# KeeWatch_Power_Supply.net
KiCad netlist of a schematic drawn in Altium Designer
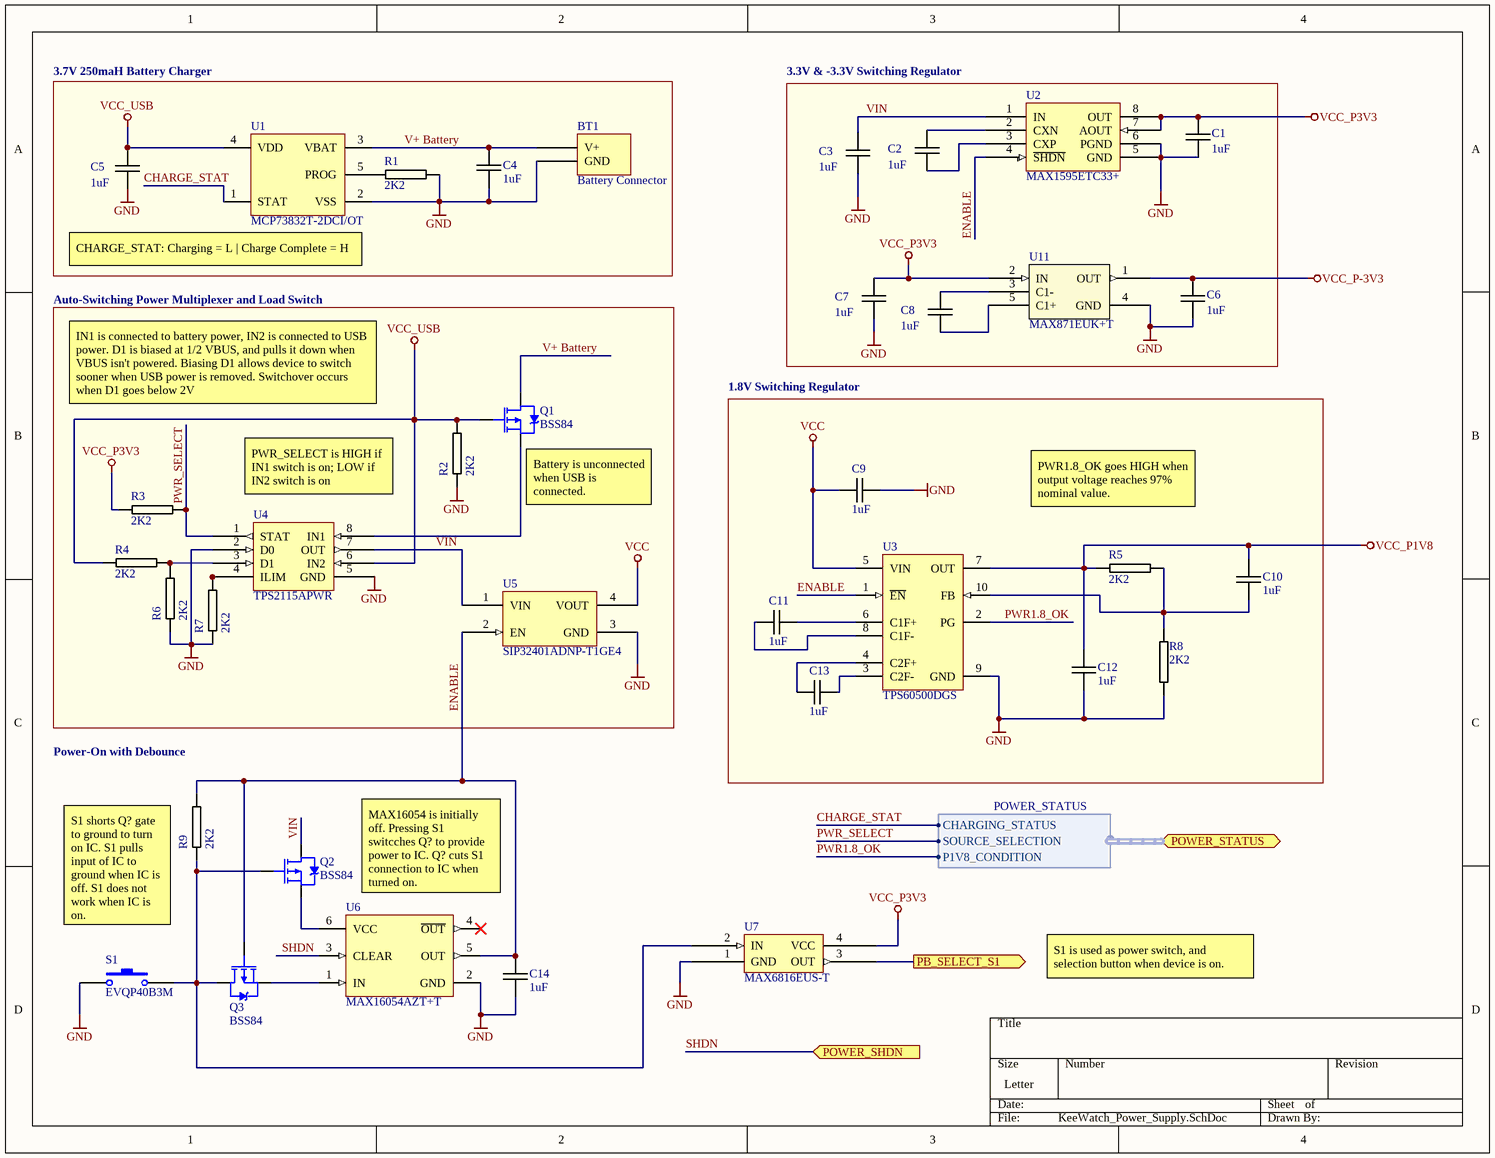
[diagram p0: KeeWatch_Power_Supply.SchDoc]

(export (version "E")
  (design (tool "Eeschema 10.0.6"))
  (components
    (comp (ref "BT1")
      (value "Battery Connector")
      (footprint "BATTERY CONNECTOR")
      (description "3.7V 250maH Battery Connector")
      (libsource (lib "WATCH") (part "Battery Connector"))
    )
    (comp (ref "C1")
      (value "1uF")
      (footprint "0603-Cap")
      (description "CAPACITOR 0603 CERAMIC")
      (libsource (lib "Passives") (part "0603-Cap"))
    )
    (comp (ref "C2")
      (value "1uF")
      (footprint "0603-Cap")
      (description "CAPACITOR 0603 CERAMIC")
      (libsource (lib "Passives") (part "0603-Cap"))
    )
    (comp (ref "C3")
      (value "1uF")
      (footprint "0603-Cap")
      (description "CAPACITOR 0603 CERAMIC")
      (libsource (lib "Passives") (part "0603-Cap"))
    )
    (comp (ref "C4")
      (value "1uF")
      (footprint "0603-Cap")
      (description "CAPACITOR 0603 CERAMIC")
      (libsource (lib "Passives") (part "0603-Cap"))
    )
    (comp (ref "C5")
      (value "1uF")
      (footprint "0603-Cap")
      (description "CAPACITOR 0603 CERAMIC")
      (libsource (lib "Passives") (part "0603-Cap"))
    )
    (comp (ref "C6")
      (value "1uF")
      (footprint "0603-Cap")
      (description "CAPACITOR 0603 CERAMIC")
      (libsource (lib "Passives") (part "0603-Cap"))
    )
    (comp (ref "C7")
      (value "1uF")
      (footprint "0603-Cap")
      (description "CAPACITOR 0603 CERAMIC")
      (libsource (lib "Passives") (part "0603-Cap"))
    )
    (comp (ref "C8")
      (value "1uF")
      (footprint "0603-Cap")
      (description "CAPACITOR 0603 CERAMIC")
      (libsource (lib "Passives") (part "0603-Cap"))
    )
    (comp (ref "C9")
      (value "1uF")
      (footprint "0603-Cap")
      (description "CAPACITOR 0603 CERAMIC")
      (libsource (lib "Passives") (part "0603-Cap"))
    )
    (comp (ref "C10")
      (value "1uF")
      (footprint "0603-Cap")
      (description "CAPACITOR 0603 CERAMIC")
      (libsource (lib "Passives") (part "0603-Cap"))
    )
    (comp (ref "C11")
      (value "1uF")
      (footprint "0603-Cap")
      (description "CAPACITOR 0603 CERAMIC")
      (libsource (lib "Passives") (part "0603-Cap"))
    )
    (comp (ref "C12")
      (value "1uF")
      (footprint "0603-Cap")
      (description "CAPACITOR 0603 CERAMIC")
      (libsource (lib "Passives") (part "0603-Cap"))
    )
    (comp (ref "C13")
      (value "1uF")
      (footprint "0603-Cap")
      (description "CAPACITOR 0603 CERAMIC")
      (libsource (lib "Passives") (part "0603-Cap"))
    )
    (comp (ref "C14")
      (value "1uF")
      (footprint "0603-Cap")
      (description "CAPACITOR 0603 CERAMIC")
      (libsource (lib "Passives") (part "0603-Cap"))
    )
    (comp (ref "Q1") (value "BSS84") (footprint "SOT23-GDS") (libsource (lib "WATCH") (part "BSS84")))
    (comp (ref "Q2") (value "BSS84") (footprint "SOT23-GDS") (libsource (lib "WATCH") (part "BSS84")))
    (comp (ref "Q3") (value "BSS84") (footprint "SOT23-GDS") (libsource (lib "WATCH") (part "BSS84")))
    (comp (ref "R1")
      (value "2K2")
      (footprint "0603-RES")
      (description "GENERIC RESISTOR 0603")
      (libsource (lib "Passives") (part "0603-Res"))
    )
    (comp (ref "R2")
      (value "2K2")
      (footprint "0603-RES")
      (description "GENERIC RESISTOR 0603")
      (libsource (lib "Passives") (part "0603-Res"))
    )
    (comp (ref "R3")
      (value "2K2")
      (footprint "0603-RES")
      (description "GENERIC RESISTOR 0603")
      (libsource (lib "Passives") (part "0603-Res"))
    )
    (comp (ref "R4")
      (value "2K2")
      (footprint "0603-RES")
      (description "GENERIC RESISTOR 0603")
      (libsource (lib "Passives") (part "0603-Res"))
    )
    (comp (ref "R5")
      (value "2K2")
      (footprint "0603-RES")
      (description "GENERIC RESISTOR 0603")
      (libsource (lib "Passives") (part "0603-Res"))
    )
    (comp (ref "R6")
      (value "2K2")
      (footprint "0603-RES")
      (description "GENERIC RESISTOR 0603")
      (libsource (lib "Passives") (part "0603-Res"))
    )
    (comp (ref "R7")
      (value "2K2")
      (footprint "0603-RES")
      (description "GENERIC RESISTOR 0603")
      (libsource (lib "Passives") (part "0603-Res"))
    )
    (comp (ref "R8")
      (value "2K2")
      (footprint "0603-RES")
      (description "GENERIC RESISTOR 0603")
      (libsource (lib "Passives") (part "0603-Res"))
    )
    (comp (ref "R9")
      (value "2K2")
      (footprint "0603-RES")
      (description "GENERIC RESISTOR 0603")
      (libsource (lib "Passives") (part "0603-Res"))
    )
    (comp (ref "S1") (value "EVQP40B3M") (footprint "EVQP4") (libsource (lib "WATCH") (part "EVQP40B3M")))
    (comp (ref "U1")
      (value "MCP73832T-2DCI/OT")
      (footprint "SOT-23-OT5_N")
      (fields (field (name "MANUFACTURER") "Microchip"))
      (libsource (lib "WATCH") (part "MCP73832T-2DCI/OT"))
    )
    (comp (ref "U2")
      (value "MAX1595ETC33+")
      (footprint "TQFN12")
      (description "Regulated 3.3V/5.0V Step-Up/Step-Down Charge Pump")
      (libsource (lib "WATCH") (part "MAX1595ETC33+"))
    )
    (comp (ref "U3")
      (value "TPS60500DGS")
      (footprint "TI-DGS10_N")
      (fields (field (name "MANUFACTURER") "Texas Instruments"))
      (libsource (lib "WATCH") (part "TPS60500DGS"))
    )
    (comp (ref "U4")
      (value "TPS2115APWR")
      (footprint "TSSOP-8")
      (description "Auto-switching Power MUX")
      (libsource (lib "WATCH") (part "TPS2115APWR"))
    )
    (comp (ref "U5")
      (value "SIP32401ADNP-T1GE4")
      (footprint "TDFN4")
      (description "1.1 V to 5.5 V, Slew Rate Controlled Load SwitcH")
      (libsource (lib "WATCH") (part "SIP32401ADNP-T1GE4"))
    )
    (comp (ref "U6")
      (value "MAX16054AZT+T")
      (footprint "Z6+1_N")
      (libsource (lib "WATCH") (part "MAX16054AZT+T"))
    )
    (comp (ref "U7")
      (value "MAX6816EUS-T")
      (footprint "SOT143B")
      (libsource (lib "Schlib2") (part "MAX6816EUS-T"))
    )
    (comp (ref "U11")
      (value "MAX871EUK+T")
      (footprint "SOT-23-OT5_N")
      (description "Switched-Capacitor Voltage Inverters")
      (fields (field (name "MANUFACTURER_PART_NUMBER") "max871euk+t"))
      (libsource (lib "WATCH") (part "MAX871EUK+T"))
    )
  )
  (nets
    (net (code "2") (name "/CHARGE_STAT") (class "Default")
      (node (ref "U1") (pin "1") (pinfunction "STAT_1") (pintype "open_collector"))
    )
    (net (code "3") (name "/ENABLE") (class "Default")
      (node (ref "C14") (pin "1") (pintype "passive"))
      (node (ref "Q3") (pin "1") (pinfunction "G_1") (pintype "passive"))
      (node (ref "R9") (pin "1") (pintype "passive"))
      (node (ref "U2") (pin "4") (pinfunction "~{SHDN}_4") (pintype "input"))
      (node (ref "U3") (pin "1") (pinfunction "~{EN}_1") (pintype "input"))
      (node (ref "U5") (pin "2") (pinfunction "EN_2") (pintype "input"))
      (node (ref "U6") (pin "5") (pinfunction "OUT_5") (pintype "output"))
    )
    (net (code "4") (name "/PB_SELECT_S1") (class "Default")
      (node (ref "U7") (pin "3") (pinfunction "OUT_3") (pintype "output"))
    )
    (net (code "5") (name "/PWR1.8_OK") (class "Default")
      (node (ref "U3") (pin "2") (pinfunction "PG_2") (pintype "open_collector"))
    )
    (net (code "6") (name "/PWR_SELECT") (class "Default")
      (node (ref "R3") (pin "2") (pintype "passive"))
      (node (ref "U4") (pin "1") (pinfunction "STAT_1") (pintype "output"))
    )
    (net (code "7") (name "/SHDN") (class "Default")
      (node (ref "U6") (pin "3") (pinfunction "CLEAR_3") (pintype "input"))
    )
    (net (code "8") (name "/V+ Battery") (class "Default")
      (node (ref "BT1") (pin "1") (pinfunction "V+_1") (pintype "passive"))
      (node (ref "C4") (pin "2") (pintype "passive"))
      (node (ref "Q1") (pin "2") (pinfunction "D_2") (pintype "passive"))
      (node (ref "U1") (pin "3") (pinfunction "VBAT_3") (pintype "power_in"))
    )
    (net (code "9") (name "/VIN") (class "Default")
      (node (ref "C3") (pin "1") (pintype "passive"))
      (node (ref "Q2") (pin "2") (pinfunction "D_2") (pintype "passive"))
      (node (ref "U2") (pin "1") (pinfunction "IN_1") (pintype "power_in"))
      (node (ref "U4") (pin "7") (pinfunction "OUT_7") (pintype "output"))
      (node (ref "U5") (pin "1") (pinfunction "VIN_1") (pintype "power_in"))
    )
    (net (code "11") (name "GND") (class "Default")
      (node (ref "BT1") (pin "2") (pinfunction "GND_2") (pintype "passive"))
      (node (ref "C1") (pin "2") (pintype "passive"))
      (node (ref "C12") (pin "1") (pintype "passive"))
      (node (ref "C14") (pin "2") (pintype "passive"))
      (node (ref "C3") (pin "2") (pintype "passive"))
      (node (ref "C4") (pin "1") (pintype "passive"))
      (node (ref "C5") (pin "2") (pintype "passive"))
      (node (ref "C6") (pin "2") (pintype "passive"))
      (node (ref "C7") (pin "2") (pintype "passive"))
      (node (ref "C9") (pin "2") (pintype "passive"))
      (node (ref "R1") (pin "2") (pintype "passive"))
      (node (ref "R2") (pin "2") (pintype "passive"))
      (node (ref "R6") (pin "2") (pintype "passive"))
      (node (ref "R7") (pin "2") (pintype "passive"))
      (node (ref "R8") (pin "1") (pintype "passive"))
      (node (ref "S1") (pin "1") (pinfunction "1_1") (pintype "passive"))
      (node (ref "U1") (pin "2") (pinfunction "VSS_2") (pintype "power_in"))
      (node (ref "U11") (pin "4") (pinfunction "GND_4") (pintype "power_in"))
      (node (ref "U2") (pin "5") (pinfunction "GND_5") (pintype "passive"))
      (node (ref "U2") (pin "6") (pinfunction "PGND_6") (pintype "passive"))
      (node (ref "U3") (pin "9") (pinfunction "GND_9") (pintype "power_in"))
      (node (ref "U4") (pin "2") (pinfunction "D0_2") (pintype "input"))
      (node (ref "U4") (pin "5") (pinfunction "GND_5") (pintype "passive"))
      (node (ref "U5") (pin "3") (pinfunction "GND_3") (pintype "passive"))
      (node (ref "U6") (pin "2") (pinfunction "GND_2") (pintype "power_in"))
      (node (ref "U7") (pin "1") (pinfunction "GND_1") (pintype "passive"))
    )
    (net (code "12") (name "Net-(Q1-S)") (class "Default")
      (node (ref "Q1") (pin "3") (pinfunction "S_3") (pintype "passive"))
      (node (ref "U4") (pin "8") (pinfunction "IN1_8") (pintype "input"))
    )
    (net (code "13") (name "Net-(Q2-G)") (class "Default")
      (node (ref "Q2") (pin "1") (pinfunction "G_1") (pintype "passive"))
      (node (ref "Q3") (pin "2") (pinfunction "D_2") (pintype "passive"))
      (node (ref "R9") (pin "2") (pintype "passive"))
      (node (ref "S1") (pin "2") (pinfunction "2_2") (pintype "passive"))
      (node (ref "U7") (pin "2") (pinfunction "IN_2") (pintype "input"))
    )
    (net (code "14") (name "Net-(Q2-S)") (class "Default")
      (node (ref "Q2") (pin "3") (pinfunction "S_3") (pintype "passive"))
      (node (ref "U6") (pin "6") (pinfunction "VCC_6") (pintype "power_in"))
    )
    (net (code "15") (name "Net-(Q3-S)") (class "Default")
      (node (ref "Q3") (pin "3") (pinfunction "S_3") (pintype "passive"))
      (node (ref "U6") (pin "1") (pinfunction "IN_1") (pintype "input"))
    )
    (net (code "16") (name "Net-(U1-PROG)") (class "Default")
      (node (ref "R1") (pin "1") (pintype "passive"))
      (node (ref "U1") (pin "5") (pinfunction "PROG_5") (pintype "passive"))
    )
    (net (code "17") (name "Net-(U2-CXN)") (class "Default")
      (node (ref "C2") (pin "1") (pintype "passive"))
      (node (ref "U2") (pin "2") (pinfunction "CXN_2") (pintype "passive"))
    )
    (net (code "18") (name "Net-(U2-CXP)") (class "Default")
      (node (ref "C2") (pin "2") (pintype "passive"))
      (node (ref "U2") (pin "3") (pinfunction "CXP_3") (pintype "passive"))
    )
    (net (code "19") (name "Net-(U3-C1F+)") (class "Default")
      (node (ref "C11") (pin "2") (pintype "passive"))
      (node (ref "U3") (pin "6") (pinfunction "C1F+_6") (pintype "passive"))
    )
    (net (code "20") (name "Net-(U3-C1F-)") (class "Default")
      (node (ref "C11") (pin "1") (pintype "passive"))
      (node (ref "U3") (pin "8") (pinfunction "C1F-_8") (pintype "passive"))
    )
    (net (code "21") (name "Net-(U3-C2F+)") (class "Default")
      (node (ref "C13") (pin "1") (pintype "passive"))
      (node (ref "U3") (pin "4") (pinfunction "C2F+_4") (pintype "passive"))
    )
    (net (code "22") (name "Net-(U3-C2F-)") (class "Default")
      (node (ref "C13") (pin "2") (pintype "passive"))
      (node (ref "U3") (pin "3") (pinfunction "C2F-_3") (pintype "passive"))
    )
    (net (code "23") (name "Net-(U3-FB)") (class "Default")
      (node (ref "C10") (pin "1") (pintype "passive"))
      (node (ref "R5") (pin "2") (pintype "passive"))
      (node (ref "R8") (pin "2") (pintype "passive"))
      (node (ref "U3") (pin "10") (pinfunction "FB_10") (pintype "input"))
    )
    (net (code "24") (name "Net-(U4-D1)") (class "Default")
      (node (ref "R4") (pin "2") (pintype "passive"))
      (node (ref "R6") (pin "1") (pintype "passive"))
      (node (ref "U4") (pin "3") (pinfunction "D1_3") (pintype "input"))
    )
    (net (code "25") (name "Net-(U4-ILIM)") (class "Default")
      (node (ref "R7") (pin "1") (pintype "passive"))
      (node (ref "U4") (pin "4") (pinfunction "ILIM_4") (pintype "passive"))
    )
    (net (code "26") (name "Net-(U11-C1+)") (class "Default")
      (node (ref "C8") (pin "2") (pintype "passive"))
      (node (ref "U11") (pin "5") (pinfunction "C1+_5") (pintype "passive"))
    )
    (net (code "27") (name "Net-(U11-C1-)") (class "Default")
      (node (ref "C8") (pin "1") (pintype "passive"))
      (node (ref "U11") (pin "3") (pinfunction "C1-_3") (pintype "passive"))
    )
    (net (code "28") (name "VCC") (class "Default")
      (node (ref "C9") (pin "1") (pintype "passive"))
      (node (ref "U3") (pin "5") (pinfunction "VIN_5") (pintype "power_in"))
      (node (ref "U5") (pin "4") (pinfunction "VOUT_4") (pintype "power_in"))
    )
    (net (code "29") (name "VCC_P-3V3") (class "Default")
      (node (ref "C6") (pin "1") (pintype "passive"))
      (node (ref "U11") (pin "1") (pinfunction "OUT_1") (pintype "output"))
    )
    (net (code "30") (name "VCC_P1V8") (class "Default")
      (node (ref "C10") (pin "2") (pintype "passive"))
      (node (ref "C12") (pin "2") (pintype "passive"))
      (node (ref "R5") (pin "1") (pintype "passive"))
      (node (ref "U3") (pin "7") (pinfunction "OUT_7") (pintype "power_in"))
    )
    (net (code "31") (name "VCC_P3V3") (class "Default")
      (node (ref "C1") (pin "1") (pintype "passive"))
      (node (ref "C7") (pin "1") (pintype "passive"))
      (node (ref "R3") (pin "1") (pintype "passive"))
      (node (ref "U11") (pin "2") (pinfunction "IN_2") (pintype "input"))
      (node (ref "U2") (pin "7") (pinfunction "AOUT_7") (pintype "input"))
      (node (ref "U2") (pin "8") (pinfunction "OUT_8") (pintype "passive"))
      (node (ref "U7") (pin "4") (pinfunction "VCC_4") (pintype "power_in"))
    )
    (net (code "32") (name "VCC_USB") (class "Default")
      (node (ref "C5") (pin "1") (pintype "passive"))
      (node (ref "Q1") (pin "1") (pinfunction "G_1") (pintype "passive"))
      (node (ref "R2") (pin "1") (pintype "passive"))
      (node (ref "R4") (pin "1") (pintype "passive"))
      (node (ref "U1") (pin "4") (pinfunction "VDD_4") (pintype "power_in"))
      (node (ref "U4") (pin "6") (pinfunction "IN2_6") (pintype "input"))
    )
    (net (code "33") (name "unconnected-(U6-~{OUT}-Pad4)") (class "Default")
      (node (ref "U6") (pin "4") (pinfunction "~{OUT}_4") (pintype "output+no_connect"))
    )
  )
)
